# Schematic.net
KiCad netlist of a schematic drawn in Altium Designer
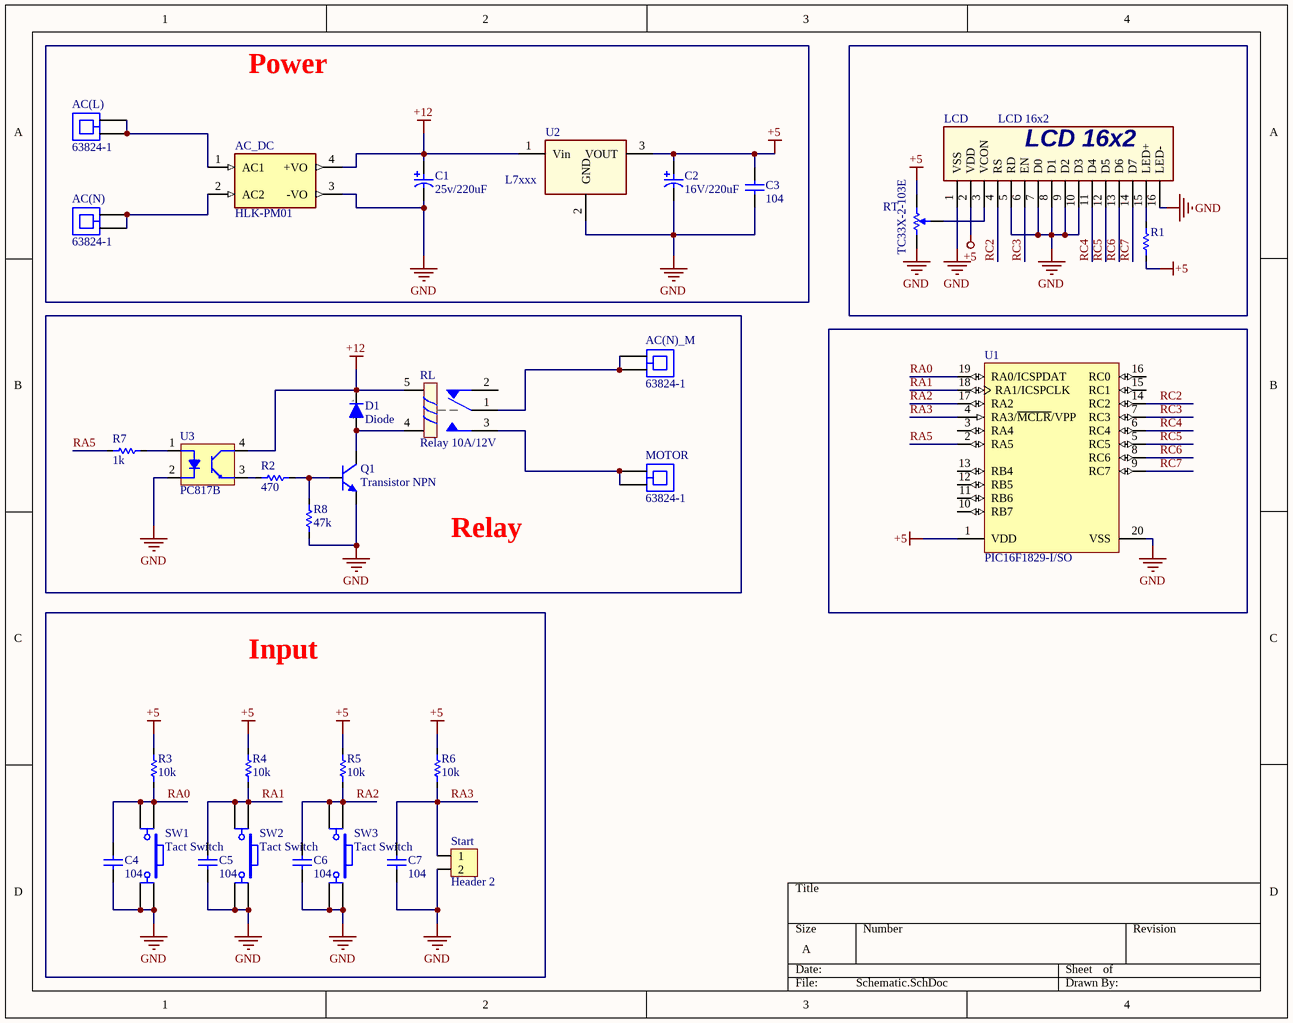
[diagram p0: Schematic.SchDoc]

(export (version "E")
  (design (tool "Eeschema 10.0.6"))
  (components
    (comp (ref "AC(L)")
      (value "63824-1")
      (footprint "TECO-63824-1_V")
      (description "Printed Circuit Board Terminal and Disconnect, 2-Pin THD, RoHS, Tape and Reel")
      (fields (field (name "MANUFACTURER") "TE Connectivity"))
      (libsource (lib "Altium Content Vault") (part "TECO-63824-1"))
    )
    (comp (ref "AC(N)")
      (value "63824-1")
      (footprint "TECO-63824-1_V")
      (description "Printed Circuit Board Terminal and Disconnect, 2-Pin THD, RoHS, Tape and Reel")
      (fields (field (name "MANUFACTURER") "TE Connectivity"))
      (libsource (lib "Altium Content Vault") (part "TECO-63824-1"))
    )
    (comp (ref "AC(N)_M")
      (value "63824-1")
      (footprint "TECO-63824-1_V")
      (description "Printed Circuit Board Terminal and Disconnect, 2-Pin THD, RoHS, Tape and Reel")
      (fields (field (name "MANUFACTURER") "TE Connectivity"))
      (libsource (lib "Altium Content Vault") (part "TECO-63824-1"))
    )
    (comp (ref "AC_DC")
      (value "HLK-PM01")
      (footprint "CONV_HLK-PM01")
      (fields (field (name "MF") "Hi-link") (field (name "MP") "hlk-pm01"))
      (libsource (lib "HLK-PM01") (part "HLK-PM01"))
    )
    (comp (ref "C1")
      (value "25v/220uF")
      (footprint "C SMD ALU (D8)")
      (description "Capacitor pol")
      (libsource (lib "BKIT4U_LIB_NEW") (part "Capacitor"))
    )
    (comp (ref "C2")
      (value "16V/220uF")
      (footprint "C SMD ALU (D8)")
      (description "Capacitor pol")
      (libsource (lib "BKIT4U_LIB_NEW") (part "Capacitor"))
    )
    (comp (ref "C3")
      (value "104")
      (footprint "C 0805 (2012)")
      (description "Capacitor non-pol")
      (libsource (lib "BKIT4U_LIB_NEW") (part "Capacitor NP"))
    )
    (comp (ref "C4")
      (value "104")
      (footprint "C 0805 (2012)")
      (description "Capacitor non-pol")
      (libsource (lib "BKIT4U_LIB_NEW") (part "Capacitor NP"))
    )
    (comp (ref "C5")
      (value "104")
      (footprint "C 0805 (2012)")
      (description "Capacitor non-pol")
      (libsource (lib "BKIT4U_LIB_NEW") (part "Capacitor NP"))
    )
    (comp (ref "C6")
      (value "104")
      (footprint "C 0805 (2012)")
      (description "Capacitor non-pol")
      (libsource (lib "BKIT4U_LIB_NEW") (part "Capacitor NP"))
    )
    (comp (ref "C7")
      (value "104")
      (footprint "C 0805 (2012)")
      (description "Capacitor non-pol")
      (libsource (lib "BKIT4U_LIB_NEW") (part "Capacitor NP"))
    )
    (comp (ref "D1")
      (value "Diode")
      (footprint "SOD-80")
      (description "Default Diode")
      (fields (field (name "PUBLISHER") "Altium Limited"))
      (libsource (lib "BKIT4U_LIB_NEW") (part "Diode"))
    )
    (comp (ref "LCD")
      (value "LCD 16x2")
      (footprint "LCD 16x2")
      (description "Character LCD 16x2")
      (libsource (lib "BKIT4U_LIB_NEW") (part "LCD 16x2"))
    )
    (comp (ref "MOTOR")
      (value "63824-1")
      (footprint "TECO-63824-1_V")
      (description "Printed Circuit Board Terminal and Disconnect, 2-Pin THD, RoHS, Tape and Reel")
      (fields (field (name "MANUFACTURER") "TE Connectivity"))
      (libsource (lib "Altium Content Vault") (part "TECO-63824-1"))
    )
    (comp (ref "Q1")
      (value "Transistor NPN")
      (footprint "SOT-23")
      (description "NPN Bipolar Transistor")
      (libsource (lib "BKIT4U_LIB_NEW") (part "Transistor NPN"))
    )
    (comp (ref "R1")
      (value "470")
      (footprint "R 0805 (2012)")
      (description "Resistor")
      (fields (field (name "PUBLISHER") "Altium Limited"))
      (libsource (lib "BKIT4U_LIB_NEW") (part "Resistor"))
    )
    (comp (ref "R2")
      (value "470")
      (footprint "R 0805 (2012)")
      (description "Resistor")
      (fields (field (name "PUBLISHER") "Altium Limited"))
      (libsource (lib "BKIT4U_LIB_NEW") (part "Resistor"))
    )
    (comp (ref "R3")
      (value "10k")
      (footprint "R 0805 (2012)")
      (description "Resistor")
      (fields (field (name "PUBLISHER") "Altium Limited"))
      (libsource (lib "BKIT4U_LIB_NEW") (part "Resistor"))
    )
    (comp (ref "R4")
      (value "10k")
      (footprint "R 0805 (2012)")
      (description "Resistor")
      (fields (field (name "PUBLISHER") "Altium Limited"))
      (libsource (lib "BKIT4U_LIB_NEW") (part "Resistor"))
    )
    (comp (ref "R5")
      (value "10k")
      (footprint "R 0805 (2012)")
      (description "Resistor")
      (fields (field (name "PUBLISHER") "Altium Limited"))
      (libsource (lib "BKIT4U_LIB_NEW") (part "Resistor"))
    )
    (comp (ref "R6")
      (value "10k")
      (footprint "R 0805 (2012)")
      (description "Resistor")
      (fields (field (name "PUBLISHER") "Altium Limited"))
      (libsource (lib "BKIT4U_LIB_NEW") (part "Resistor"))
    )
    (comp (ref "R7")
      (value "1k")
      (footprint "R 0805 (2012)")
      (description "Resistor")
      (fields (field (name "PUBLISHER") "Altium Limited"))
      (libsource (lib "BKIT4U_LIB_NEW") (part "Resistor"))
    )
    (comp (ref "R8")
      (value "47k")
      (footprint "R 0805 (2012)")
      (description "Resistor")
      (fields (field (name "PUBLISHER") "Altium Limited"))
      (libsource (lib "BKIT4U_LIB_NEW") (part "Resistor"))
    )
    (comp (ref "RL")
      (value "Relay 10A/12V")
      (footprint "RL_SPDT_10A")
      (description "Relay SPDT,10A - 12VDC 5 Pin")
      (libsource (lib "BKIT4U_LIB_NEW") (part "Relay 1"))
    )
    (comp (ref "RT")
      (value "TC33X-2-103E")
      (footprint "BOUR-TC33X-2_V")
      (description "Trimming Potentiometer, 10000 Ohm, -40 to 100 degC, 3-Pin SMD, RoHS, Tape and Reel")
      (fields (field (name "TOLERANCE") "25%") (field (name "MANUFACTURER") "Bourns"))
      (libsource (lib "Altium Content Vault") (part "RES-ADJ-3_A"))
    )
    (comp (ref "Start")
      (value "Header 2")
      (footprint "XH2.54-2P")
      (description "Header, 2-Pin")
      (fields (field (name "PUBLISHER") "Altium Limited"))
      (libsource (lib "BKIT4U_LIB_NEW") (part "Header 2"))
    )
    (comp (ref "SW1")
      (value "Tact Switch")
      (footprint "SW/4/DIP 12x12x7")
      (description "Tact switch 4 pin")
      (libsource (lib "BKIT4U_LIB_NEW") (part "SW SPST-4"))
    )
    (comp (ref "SW2")
      (value "Tact Switch")
      (footprint "SW/4/DIP 12x12x7")
      (description "Tact switch 4 pin")
      (libsource (lib "BKIT4U_LIB_NEW") (part "SW SPST-4"))
    )
    (comp (ref "SW3")
      (value "Tact Switch")
      (footprint "SW/4/DIP 12x12x7")
      (description "Tact switch 4 pin")
      (libsource (lib "BKIT4U_LIB_NEW") (part "SW SPST-4"))
    )
    (comp (ref "U1")
      (value "PIC16F1829-I/SO")
      (footprint "MCHP-SOIC-SO20_N")
      (fields (field (name "MANUFACTURER") "Microchip"))
      (libsource (lib "Altium Content Vault") (part "MCHP-PIC16F150X_182X-20"))
    )
    (comp (ref "U2")
      (value "L7xxx")
      (footprint "TO-252 (DPAK)")
      (description "LDO Fixed Voltage regulator")
      (libsource (lib "BKIT4U_LIB_NEW") (part "L7xxx"))
    )
    (comp (ref "U3")
      (value "PC817B")
      (footprint "SOIC-4-GULLWING")
      (libsource (lib "BKIT4U_LIB_NEW") (part "Opto PC817B"))
    )
  )
  (nets
    (net (code "1") (name "+5") (class "Default")
      (node (ref "C2") (pin "1") (pinfunction "1_1") (pintype "passive"))
      (node (ref "C3") (pin "1") (pinfunction "1_1") (pintype "passive"))
      (node (ref "LCD") (pin "2") (pinfunction "VDD_2") (pintype "passive"))
      (node (ref "R1") (pin "1") (pinfunction "1_1") (pintype "passive"))
      (node (ref "R3") (pin "2") (pinfunction "2_2") (pintype "passive"))
      (node (ref "R4") (pin "2") (pinfunction "2_2") (pintype "passive"))
      (node (ref "R5") (pin "2") (pinfunction "2_2") (pintype "passive"))
      (node (ref "R6") (pin "2") (pinfunction "2_2") (pintype "passive"))
      (node (ref "RT") (pin "3") (pinfunction "3_3") (pintype "passive"))
      (node (ref "U1") (pin "1") (pinfunction "VDD_1") (pintype "power_in"))
      (node (ref "U2") (pin "3") (pinfunction "VOUT_3") (pintype "passive"))
    )
    (net (code "2") (name "+12") (class "Default")
      (node (ref "AC_DC") (pin "4") (pinfunction "+VO_4") (pintype "output"))
      (node (ref "C1") (pin "1") (pinfunction "1_1") (pintype "passive"))
      (node (ref "D1") (pin "1") (pinfunction "Cathode_1") (pintype "passive"))
      (node (ref "RL") (pin "5") (pinfunction "5_5") (pintype "passive"))
      (node (ref "U2") (pin "1") (pinfunction "Vin_1") (pintype "power_in"))
      (node (ref "U3") (pin "4") (pinfunction "C_4") (pintype "passive"))
    )
    (net (code "3") (name "/RA0") (class "Default")
      (node (ref "C4") (pin "1") (pinfunction "1_1") (pintype "passive"))
      (node (ref "R3") (pin "1") (pinfunction "1_1") (pintype "passive"))
      (node (ref "SW1") (pin "1") (pinfunction "1_1") (pintype "passive"))
      (node (ref "SW1") (pin "4") (pinfunction "2_4") (pintype "passive"))
      (node (ref "U1") (pin "19") (pinfunction "RA0/ICSPDAT_19") (pintype "bidirectional"))
    )
    (net (code "4") (name "/RA1") (class "Default")
      (node (ref "C5") (pin "1") (pinfunction "1_1") (pintype "passive"))
      (node (ref "R4") (pin "1") (pinfunction "1_1") (pintype "passive"))
      (node (ref "SW2") (pin "1") (pinfunction "1_1") (pintype "passive"))
      (node (ref "SW2") (pin "4") (pinfunction "2_4") (pintype "passive"))
      (node (ref "U1") (pin "18") (pinfunction "RA1/ICSPCLK_18") (pintype "bidirectional"))
    )
    (net (code "5") (name "/RA2") (class "Default")
      (node (ref "C6") (pin "1") (pinfunction "1_1") (pintype "passive"))
      (node (ref "R5") (pin "1") (pinfunction "1_1") (pintype "passive"))
      (node (ref "SW3") (pin "1") (pinfunction "1_1") (pintype "passive"))
      (node (ref "SW3") (pin "4") (pinfunction "2_4") (pintype "passive"))
      (node (ref "U1") (pin "17") (pinfunction "RA2_17") (pintype "bidirectional"))
    )
    (net (code "6") (name "/RA3") (class "Default")
      (node (ref "C7") (pin "1") (pinfunction "1_1") (pintype "passive"))
      (node (ref "R6") (pin "1") (pinfunction "1_1") (pintype "passive"))
      (node (ref "Start") (pin "1") (pinfunction "1_1") (pintype "passive"))
      (node (ref "U1") (pin "4") (pinfunction "RA3/~{MCLR}/VPP_4") (pintype "input"))
    )
    (net (code "7") (name "/RA5") (class "Default")
      (node (ref "R7") (pin "2") (pinfunction "2_2") (pintype "passive"))
      (node (ref "U1") (pin "2") (pinfunction "RA5_2") (pintype "bidirectional"))
    )
    (net (code "8") (name "/RC2") (class "Default")
      (node (ref "LCD") (pin "4") (pinfunction "RS_4") (pintype "passive"))
      (node (ref "U1") (pin "14") (pinfunction "RC2_14") (pintype "bidirectional"))
    )
    (net (code "9") (name "/RC3") (class "Default")
      (node (ref "LCD") (pin "6") (pinfunction "EN_6") (pintype "passive"))
      (node (ref "U1") (pin "7") (pinfunction "RC3_7") (pintype "bidirectional"))
    )
    (net (code "10") (name "/RC4") (class "Default")
      (node (ref "LCD") (pin "11") (pinfunction "D4_11") (pintype "passive"))
      (node (ref "U1") (pin "6") (pinfunction "RC4_6") (pintype "bidirectional"))
    )
    (net (code "11") (name "/RC5") (class "Default")
      (node (ref "LCD") (pin "12") (pinfunction "D5_12") (pintype "passive"))
      (node (ref "U1") (pin "5") (pinfunction "RC5_5") (pintype "bidirectional"))
    )
    (net (code "12") (name "/RC6") (class "Default")
      (node (ref "LCD") (pin "13") (pinfunction "D6_13") (pintype "passive"))
      (node (ref "U1") (pin "8") (pinfunction "RC6_8") (pintype "bidirectional"))
    )
    (net (code "13") (name "/RC7") (class "Default")
      (node (ref "LCD") (pin "14") (pinfunction "D7_14") (pintype "passive"))
      (node (ref "U1") (pin "9") (pinfunction "RC7_9") (pintype "bidirectional"))
    )
    (net (code "14") (name "GND") (class "Default")
      (node (ref "AC_DC") (pin "3") (pinfunction "-VO_3") (pintype "output"))
      (node (ref "C1") (pin "2") (pinfunction "2_2") (pintype "passive"))
      (node (ref "C2") (pin "2") (pinfunction "2_2") (pintype "passive"))
      (node (ref "C3") (pin "2") (pinfunction "2_2") (pintype "passive"))
      (node (ref "C4") (pin "2") (pinfunction "2_2") (pintype "passive"))
      (node (ref "C5") (pin "2") (pinfunction "2_2") (pintype "passive"))
      (node (ref "C6") (pin "2") (pinfunction "2_2") (pintype "passive"))
      (node (ref "C7") (pin "2") (pinfunction "2_2") (pintype "passive"))
      (node (ref "LCD") (pin "1") (pinfunction "VSS_1") (pintype "passive"))
      (node (ref "LCD") (pin "10") (pinfunction "D3_10") (pintype "passive"))
      (node (ref "LCD") (pin "16") (pinfunction "LED-_16") (pintype "passive"))
      (node (ref "LCD") (pin "5") (pinfunction "RD_5") (pintype "passive"))
      (node (ref "LCD") (pin "7") (pinfunction "D0_7") (pintype "passive"))
      (node (ref "LCD") (pin "8") (pinfunction "D1_8") (pintype "passive"))
      (node (ref "LCD") (pin "9") (pinfunction "D2_9") (pintype "passive"))
      (node (ref "Q1") (pin "2") (pinfunction "E_2") (pintype "passive"))
      (node (ref "R8") (pin "2") (pinfunction "2_2") (pintype "passive"))
      (node (ref "RT") (pin "1") (pinfunction "1_1") (pintype "passive"))
      (node (ref "SW1") (pin "2") (pinfunction "2_2") (pintype "passive"))
      (node (ref "SW1") (pin "3") (pinfunction "1_3") (pintype "passive"))
      (node (ref "SW2") (pin "2") (pinfunction "2_2") (pintype "passive"))
      (node (ref "SW2") (pin "3") (pinfunction "1_3") (pintype "passive"))
      (node (ref "SW3") (pin "2") (pinfunction "2_2") (pintype "passive"))
      (node (ref "SW3") (pin "3") (pinfunction "1_3") (pintype "passive"))
      (node (ref "Start") (pin "2") (pinfunction "2_2") (pintype "passive"))
      (node (ref "U1") (pin "20") (pinfunction "VSS_20") (pintype "power_in"))
      (node (ref "U2") (pin "2") (pinfunction "GND_2") (pintype "passive"))
      (node (ref "U3") (pin "2") (pinfunction "K_2") (pintype "passive"))
    )
    (net (code "15") (name "Net-(AC(N)_M-Pad1)") (class "Default")
      (node (ref "AC(N)_M") (pin "1") (pinfunction "1_1") (pintype "passive"))
      (node (ref "AC(N)_M") (pin "2") (pinfunction "2_2") (pintype "passive"))
      (node (ref "RL") (pin "1") (pinfunction "1_1") (pintype "passive"))
    )
    (net (code "16") (name "Net-(AC_DC-AC1)") (class "Default")
      (node (ref "AC(L)") (pin "1") (pinfunction "1_1") (pintype "passive"))
      (node (ref "AC(L)") (pin "2") (pinfunction "2_2") (pintype "passive"))
      (node (ref "AC_DC") (pin "1") (pinfunction "AC1_1") (pintype "input"))
    )
    (net (code "17") (name "Net-(AC_DC-AC2)") (class "Default")
      (node (ref "AC(N)") (pin "1") (pinfunction "1_1") (pintype "passive"))
      (node (ref "AC(N)") (pin "2") (pinfunction "2_2") (pintype "passive"))
      (node (ref "AC_DC") (pin "2") (pinfunction "AC2_2") (pintype "input"))
    )
    (net (code "18") (name "Net-(D1-Anode)") (class "Default")
      (node (ref "D1") (pin "2") (pinfunction "Anode_2") (pintype "passive"))
      (node (ref "Q1") (pin "3") (pinfunction "C_3") (pintype "passive"))
      (node (ref "RL") (pin "4") (pinfunction "4_4") (pintype "passive"))
    )
    (net (code "19") (name "Net-(LCD-LED+)") (class "Default")
      (node (ref "LCD") (pin "15") (pinfunction "LED+_15") (pintype "passive"))
      (node (ref "R1") (pin "2") (pinfunction "2_2") (pintype "passive"))
    )
    (net (code "20") (name "Net-(LCD-VCON)") (class "Default")
      (node (ref "LCD") (pin "3") (pinfunction "VCON_3") (pintype "passive"))
      (node (ref "RT") (pin "2") (pinfunction "2_2") (pintype "passive"))
    )
    (net (code "21") (name "Net-(MOTOR-Pad1)") (class "Default")
      (node (ref "MOTOR") (pin "1") (pinfunction "1_1") (pintype "passive"))
      (node (ref "MOTOR") (pin "2") (pinfunction "2_2") (pintype "passive"))
      (node (ref "RL") (pin "3") (pinfunction "3_3") (pintype "passive"))
    )
    (net (code "22") (name "Net-(Q1-B)") (class "Default")
      (node (ref "Q1") (pin "1") (pinfunction "B_1") (pintype "passive"))
      (node (ref "R2") (pin "1") (pinfunction "1_1") (pintype "passive"))
      (node (ref "R8") (pin "1") (pinfunction "1_1") (pintype "passive"))
    )
    (net (code "23") (name "Net-(U3-A)") (class "Default")
      (node (ref "R7") (pin "1") (pinfunction "1_1") (pintype "passive"))
      (node (ref "U3") (pin "1") (pinfunction "A_1") (pintype "passive"))
    )
    (net (code "24") (name "Net-(U3-E)") (class "Default")
      (node (ref "R2") (pin "2") (pinfunction "2_2") (pintype "passive"))
      (node (ref "U3") (pin "3") (pinfunction "E_3") (pintype "passive"))
    )
    (net (code "25") (name "unconnected-(RL-Pad2)") (class "Default")
      (node (ref "RL") (pin "2") (pinfunction "2_2") (pintype "passive"))
    )
    (net (code "26") (name "unconnected-(U1-RA4-Pad3)") (class "Default")
      (node (ref "U1") (pin "3") (pinfunction "RA4_3") (pintype "bidirectional"))
    )
    (net (code "27") (name "unconnected-(U1-RB4-Pad13)") (class "Default")
      (node (ref "U1") (pin "13") (pinfunction "RB4_13") (pintype "bidirectional"))
    )
    (net (code "28") (name "unconnected-(U1-RB5-Pad12)") (class "Default")
      (node (ref "U1") (pin "12") (pinfunction "RB5_12") (pintype "bidirectional"))
    )
    (net (code "29") (name "unconnected-(U1-RB6-Pad11)") (class "Default")
      (node (ref "U1") (pin "11") (pinfunction "RB6_11") (pintype "bidirectional"))
    )
    (net (code "30") (name "unconnected-(U1-RB7-Pad10)") (class "Default")
      (node (ref "U1") (pin "10") (pinfunction "RB7_10") (pintype "bidirectional"))
    )
    (net (code "31") (name "unconnected-(U1-RC0-Pad16)") (class "Default")
      (node (ref "U1") (pin "16") (pinfunction "RC0_16") (pintype "bidirectional"))
    )
    (net (code "32") (name "unconnected-(U1-RC1-Pad15)") (class "Default")
      (node (ref "U1") (pin "15") (pinfunction "RC1_15") (pintype "bidirectional"))
    )
  )
)
